# Enclosure_85x58_BHC.net
KiCad netlist of a schematic drawn in EAGLE
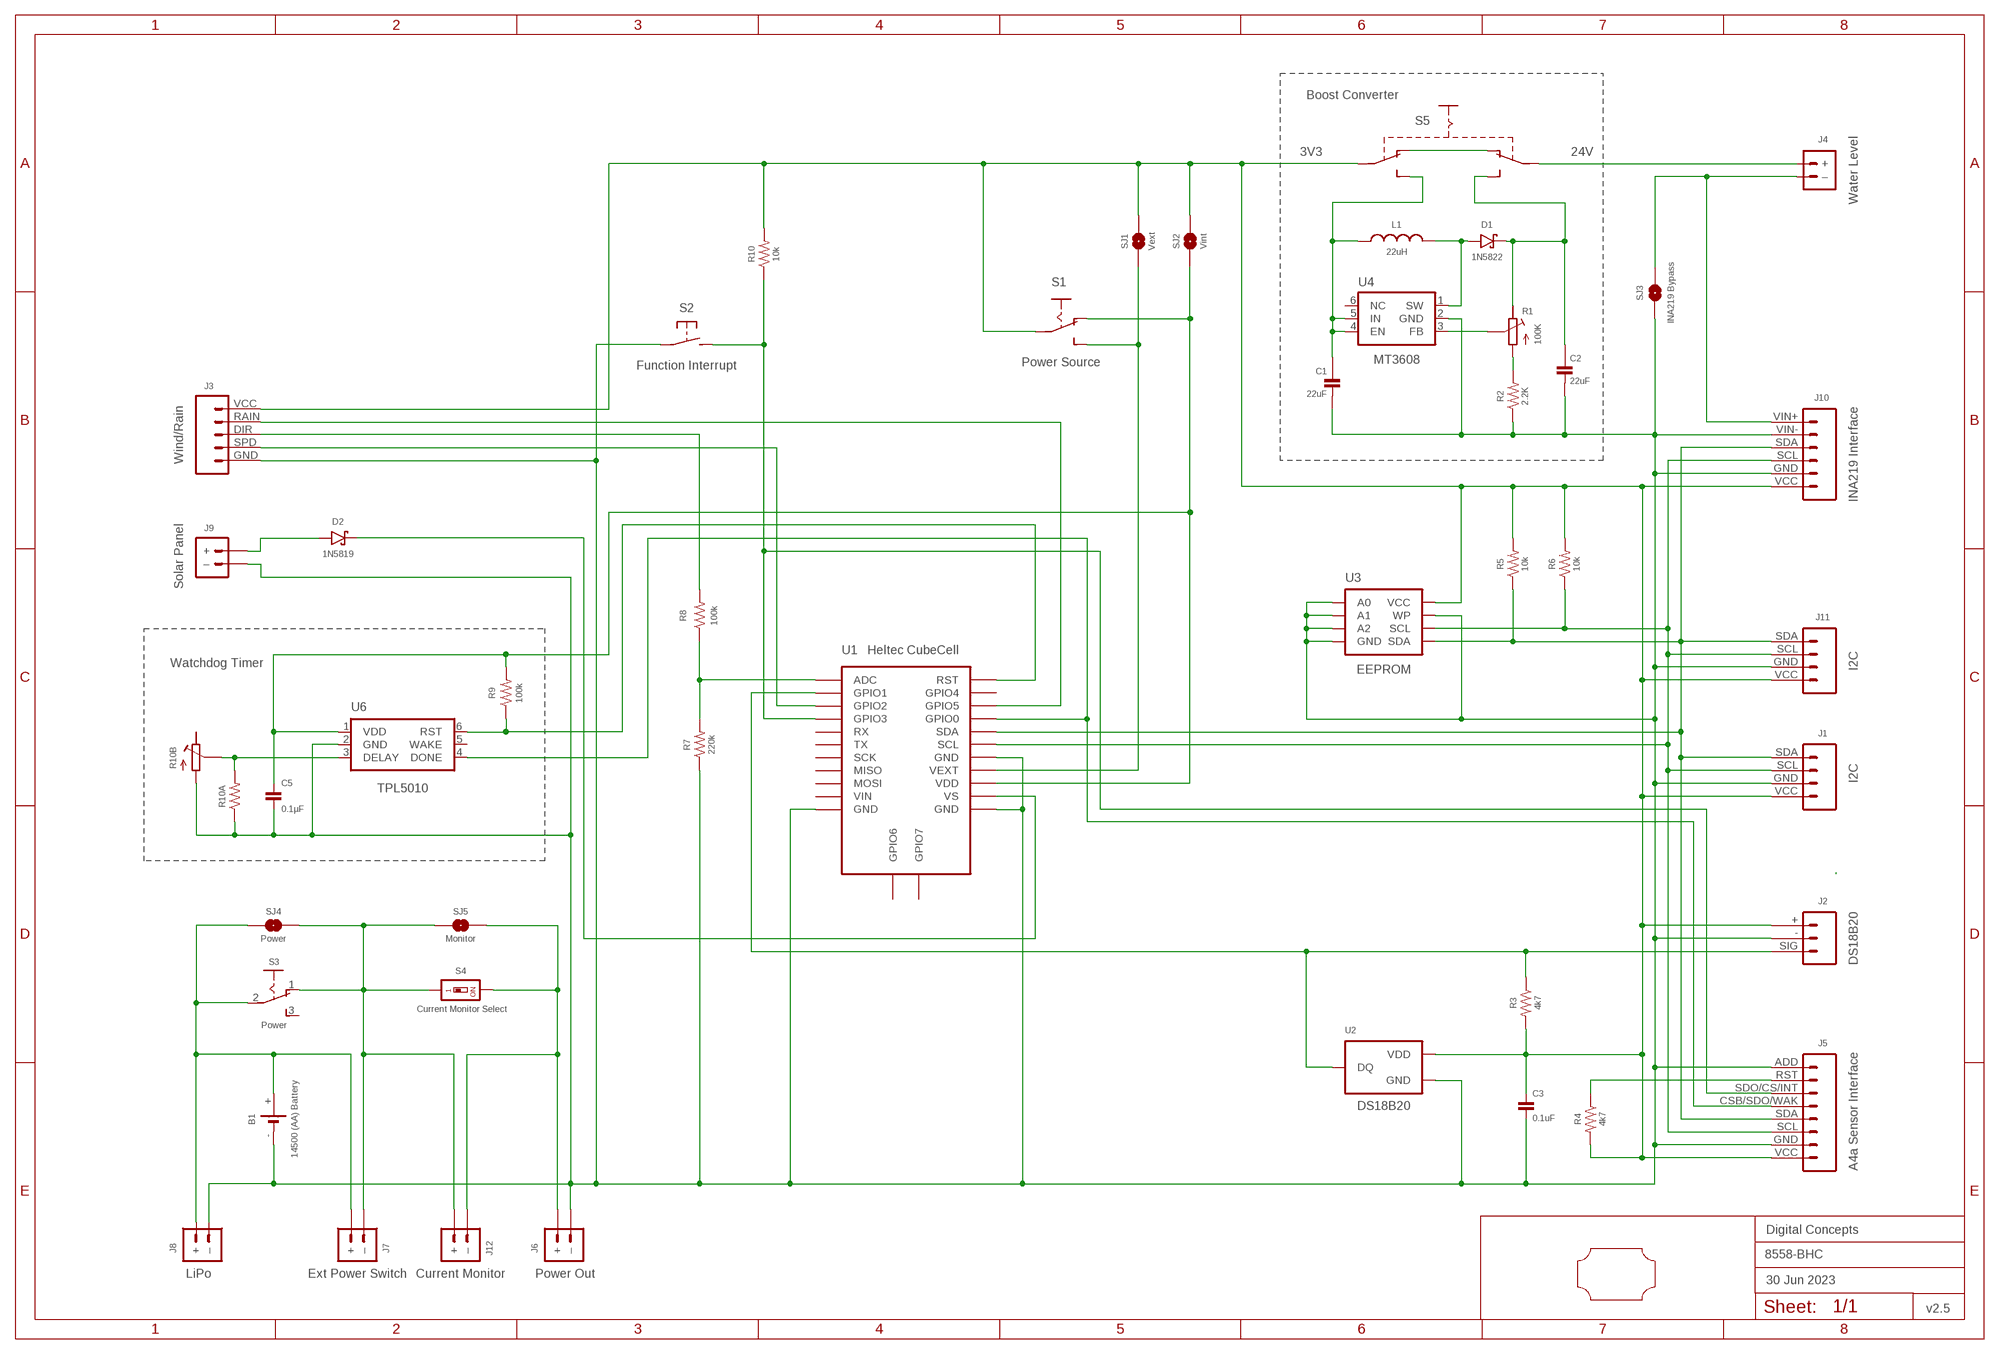
[diagram p0: schematic, sheet 1]

(export (version "E")
  (design (tool "Eeschema 10.0.6"))
  (components
    (comp (ref "B1")
      (value "14500 (AA) Battery")
      (footprint "eagle-import:BATTERY-14500")
      (libsource (lib "eagle-import") (part "BATTERY-HOLDER-14500(AA)"))
    )
    (comp (ref "C1")
      (value "22uF")
      (footprint "eagle-import:C1206")
      (libsource (lib "eagle-import") (part "CAPACITOR-1206"))
    )
    (comp (ref "C2")
      (value "22uF")
      (footprint "eagle-import:C1206")
      (libsource (lib "eagle-import") (part "CAPACITOR-1206"))
    )
    (comp (ref "C3")
      (value "0.1uF")
      (footprint "eagle-import:C0805")
      (libsource (lib "eagle-import") (part "CAPACITOR-0805"))
    )
    (comp (ref "C5")
      (value "0.1µF")
      (footprint "eagle-import:C0805")
      (libsource (lib "eagle-import") (part "CAPACITOR-0805"))
    )
    (comp (ref "D1")
      (value "1N5822")
      (footprint "eagle-import:DIODE_SMB")
      (libsource (lib "eagle-import") (part "DIODE-SCHOTTKY-1N5822"))
    )
    (comp (ref "D2")
      (value "1N5819")
      (footprint "eagle-import:SOD-123")
      (libsource (lib "eagle-import") (part "1N5819-SOD-123"))
    )
    (comp (ref "J1")
      (value "I2C")
      (footprint "eagle-import:JST-PH2.0-4-VERTICAL-I2C")
      (libsource (lib "eagle-import") (part "JST-PH2.0-4-VERTICAL-I2C"))
    )
    (comp (ref "J2")
      (value "DS18B20")
      (footprint "eagle-import:JST-PH2.0-3-VERTICAL")
      (libsource (lib "eagle-import") (part "JST-PH2.0-3-VERTICAL-DS18B20"))
    )
    (comp (ref "J3")
      (value "Wind/Rain")
      (footprint "eagle-import:JST-PH2.0-5-WEATHER")
      (libsource (lib "eagle-import") (part "JST-PH2.0-5-VERTICAL-WEATHER"))
    )
    (comp (ref "J4")
      (value "Water Level")
      (footprint "eagle-import:JST-PH2.0-2-VERTICAL=POWER")
      (libsource (lib "eagle-import") (part "JST-PH2.0-2-VERTICAL"))
    )
    (comp (ref "J5")
      (value "A4a Sensor Interface")
      (footprint "eagle-import:CONN_08-SENSOR")
      (libsource (lib "eagle-import") (part "HEADER-1X8-SENSOR"))
    )
    (comp (ref "J6")
      (value "Power Out")
      (footprint "eagle-import:JST-GH1.25-2-HORIZONTAL")
      (libsource (lib "eagle-import") (part "JST-GH1.25-2-HORIZONTAL-POWER"))
    )
    (comp (ref "J7")
      (value "Ext Power Switch")
      (footprint "eagle-import:JST-PH2.0-2-DUAL-POWER")
      (libsource (lib "eagle-import") (part "JST-PH2.0-2-DUAL-POWERJST-PTH-2"))
    )
    (comp (ref "J8")
      (value "LiPo")
      (footprint "eagle-import:JST-PH2.0-2-HORIZONTAL")
      (libsource (lib "eagle-import") (part "JST-PH2.0-2-MALE-HORIZONTALJST-PTH-2"))
    )
    (comp (ref "J9")
      (value "Solar Panel")
      (footprint "eagle-import:JST-PH2.0-2-DUAL-POWER")
      (libsource (lib "eagle-import") (part "JST-PH2.0-2-DUAL-POWERJST-PTH-2"))
    )
    (comp (ref "J10")
      (value "INA219 Interface")
      (footprint "eagle-import:CONN_06-INA219")
      (libsource (lib "eagle-import") (part "INA219-I2C-MODULE"))
    )
    (comp (ref "J11")
      (value "I2C")
      (footprint "eagle-import:JST-PH2.0-4-HORIZONTAL-I2C")
      (libsource (lib "eagle-import") (part "JST-PH2.0-4-HORIZONTAL-I2C"))
    )
    (comp (ref "J12")
      (value "Current Monitor")
      (footprint "eagle-import:JST-PH2.0-2-HORIZONTAL-POWER")
      (libsource (lib "eagle-import") (part "JST-PH2.0-2-HORIZONTAL-POWERJST-PTH-2"))
    )
    (comp (ref "L1")
      (value "22uH")
      (footprint "eagle-import:CDRH104R+6D28")
      (libsource (lib "eagle-import") (part "INDUCTOR-CDRH104R/6D28L5038P"))
    )
    (comp (ref "R1")
      (value "100K")
      (footprint "eagle-import:RTRIM64P")
      (libsource (lib "eagle-import") (part "RESISTOR-TRIMM-BAOTER-HORIZONTAL"))
    )
    (comp (ref "R2")
      (value "2.2K")
      (footprint "eagle-import:R0805")
      (libsource (lib "eagle-import") (part "RESISTORR0805"))
    )
    (comp (ref "R3")
      (value "4k7")
      (footprint "eagle-import:R0805")
      (libsource (lib "eagle-import") (part "RESISTORR0805"))
    )
    (comp (ref "R4")
      (value "4k7")
      (footprint "eagle-import:R0805")
      (libsource (lib "eagle-import") (part "RESISTORR0805"))
    )
    (comp (ref "R5")
      (value "10k")
      (footprint "eagle-import:R0805")
      (libsource (lib "eagle-import") (part "RESISTORR0805"))
    )
    (comp (ref "R6")
      (value "10k")
      (footprint "eagle-import:R0805")
      (libsource (lib "eagle-import") (part "RESISTORR0805"))
    )
    (comp (ref "R7")
      (value "220k")
      (footprint "eagle-import:R0805")
      (libsource (lib "eagle-import") (part "RESISTORR0805"))
    )
    (comp (ref "R8")
      (value "100k")
      (footprint "eagle-import:R0805")
      (libsource (lib "eagle-import") (part "RESISTORR0805"))
    )
    (comp (ref "R9")
      (value "100k")
      (footprint "eagle-import:R0805")
      (libsource (lib "eagle-import") (part "RESISTORR0805"))
    )
    (comp (ref "R10")
      (value "10k")
      (footprint "eagle-import:R0805")
      (libsource (lib "eagle-import") (part "RESISTORR0805"))
    )
    (comp (ref "R10A")
      (value "RESISTORR0805")
      (footprint "eagle-import:R0805")
      (libsource (lib "eagle-import") (part "RESISTORR0805"))
    )
    (comp (ref "R10B")
      (value "RESISTOR-TRIMM-33")
      (footprint "eagle-import:RTRIM3_3")
      (libsource (lib "eagle-import") (part "RESISTOR-TRIMM-33"))
    )
    (comp (ref "S1")
      (value "Power Source")
      (footprint "eagle-import:SWITCH-SPDT-SMT")
      (libsource (lib "eagle-import") (part "SWITCH-SLIDE-SPDT-SMT"))
    )
    (comp (ref "S2")
      (value "Function Interrupt")
      (footprint "eagle-import:SWITCH-2-PAD")
      (libsource (lib "eagle-import") (part "SWITCH-MOMENTARY-2-PIN"))
    )
    (comp (ref "S3")
      (value "Power")
      (footprint "eagle-import:SWITCH-SLIDE-SPDT")
      (libsource (lib "eagle-import") (part "SWITCH-SLIDE-SPDT"))
    )
    (comp (ref "S4")
      (value "Current Monitor Select")
      (footprint "eagle-import:SMD-001")
      (libsource (lib "eagle-import") (part "SWITCH-DIP-SWS001"))
    )
    (comp (ref "S5")
      (value "SWITCH-SLIDE-DPDT-PTH-S")
      (footprint "eagle-import:SWITCH-DPDT-PTH")
      (libsource (lib "eagle-import") (part "SWITCH-SLIDE-DPDT-PTH-S"))
    )
    (comp (ref "SJ1")
      (value "Vext")
      (footprint "eagle-import:SJ")
      (libsource (lib "eagle-import") (part "SJ"))
    )
    (comp (ref "SJ2")
      (value "Vint")
      (footprint "eagle-import:SJ-VIA-1")
      (libsource (lib "eagle-import") (part "SJ-V-1"))
    )
    (comp (ref "SJ3")
      (value "INA219 Bypass")
      (footprint "eagle-import:SJ")
      (libsource (lib "eagle-import") (part "SJ"))
    )
    (comp (ref "SJ4")
      (value "Power")
      (footprint "eagle-import:SJ")
      (libsource (lib "eagle-import") (part "SJ"))
    )
    (comp (ref "SJ5")
      (value "Monitor")
      (footprint "eagle-import:SJ")
      (libsource (lib "eagle-import") (part "SJ"))
    )
    (comp (ref "U$1")
      (value "PCB-OUTLINE-C-85X58")
      (footprint "eagle-import:PROTO-28X18-OUTLINE-C")
      (libsource (lib "eagle-import") (part "PCB-OUTLINE-C-85X58"))
    )
    (comp (ref "U1")
      (value "Heltec CubeCell")
      (footprint "eagle-import:HELTEC-CUBECELL")
      (libsource (lib "eagle-import") (part "HELTEC-CUBECELL"))
    )
    (comp (ref "U2")
      (value "DS18B20")
      (footprint "eagle-import:TO-92")
      (fields (field (name "MF") "Maxim Integrated"))
      (libsource (lib "eagle-import") (part "THERMOMETER-DS18B20"))
    )
    (comp (ref "U3")
      (value "EEPROM")
      (footprint "eagle-import:SOP-8")
      (libsource (lib "eagle-import") (part "AT24CXX-EEPROM"))
    )
    (comp (ref "U4")
      (value "MT3608")
      (footprint "eagle-import:SOT-23-6@1")
      (libsource (lib "eagle-import") (part "MT3608"))
    )
    (comp (ref "U6")
      (value "TPL5010")
      (footprint "eagle-import:SOT-23-6")
      (libsource (lib "eagle-import") (part "TPL5010DDCR"))
    )
  )
  (nets
    (net (code "1") (name "Net-(D2-PadA)") (class "Default")
      (node (ref "D2") (pin "A") (pinfunction "A_A") (pintype "passive"))
      (node (ref "J9") (pin "+") (pinfunction "+_+") (pintype "power_in"))
    )
    (net (code "2") (name "Net-(D2-PadC)") (class "Default")
      (node (ref "D2") (pin "C") (pinfunction "C_C") (pintype "passive"))
      (node (ref "U1") (pin "VS") (pinfunction "VS_VS") (pintype "bidirectional"))
    )
    (net (code "3") (name "Net-(J1-1)") (class "Default")
      (node (ref "J1") (pin "SDA") (pinfunction "1_SDA") (pintype "passive"))
      (node (ref "J10") (pin "SDA") (pinfunction "4_SDA") (pintype "passive"))
      (node (ref "J11") (pin "SDA") (pinfunction "1_SDA") (pintype "passive"))
      (node (ref "J5") (pin "SDA") (pinfunction "4_SDA") (pintype "passive"))
      (node (ref "R5") (pin "1") (pinfunction "1_1") (pintype "passive"))
      (node (ref "U1") (pin "SDA") (pinfunction "SDA_SDA") (pintype "bidirectional"))
      (node (ref "U3") (pin "P$5") (pinfunction "SDA_P$5") (pintype "bidirectional"))
    )
    (net (code "4") (name "Net-(J1-2)") (class "Default")
      (node (ref "J1") (pin "SCL") (pinfunction "2_SCL") (pintype "passive"))
      (node (ref "J10") (pin "SCL") (pinfunction "3_SCL") (pintype "passive"))
      (node (ref "J11") (pin "SCL") (pinfunction "2_SCL") (pintype "passive"))
      (node (ref "J5") (pin "SCL") (pinfunction "3_SCL") (pintype "passive"))
      (node (ref "R6") (pin "1") (pinfunction "1_1") (pintype "passive"))
      (node (ref "U1") (pin "SCL") (pinfunction "SCL_SCL") (pintype "bidirectional"))
      (node (ref "U3") (pin "P$6") (pinfunction "SCL_P$6") (pintype "bidirectional"))
    )
    (net (code "5") (name "Net-(J1-3)") (class "Default")
      (node (ref "B1") (pin "-") (pinfunction "-_-") (pintype "power_in"))
      (node (ref "C1") (pin "2") (pinfunction "2_2") (pintype "passive"))
      (node (ref "C2") (pin "2") (pinfunction "2_2") (pintype "passive"))
      (node (ref "C3") (pin "2") (pinfunction "2_2") (pintype "passive"))
      (node (ref "C5") (pin "2") (pinfunction "2_2") (pintype "passive"))
      (node (ref "J1") (pin "GND") (pinfunction "3_GND") (pintype "passive"))
      (node (ref "J10") (pin "GND") (pinfunction "2_GND") (pintype "passive"))
      (node (ref "J10") (pin "VIN-") (pinfunction "5_VIN-") (pintype "passive"))
      (node (ref "J11") (pin "GND") (pinfunction "3_GND") (pintype "passive"))
      (node (ref "J2") (pin "-") (pinfunction "2_-") (pintype "passive"))
      (node (ref "J3") (pin "GND") (pinfunction "5_GND") (pintype "passive"))
      (node (ref "J5") (pin "ADD") (pinfunction "8_ADD") (pintype "passive"))
      (node (ref "J5") (pin "GND") (pinfunction "2_GND") (pintype "passive"))
      (node (ref "J6") (pin "-") (pinfunction "–_-") (pintype "power_in"))
      (node (ref "J8") (pin "-") (pinfunction "–_-") (pintype "power_in"))
      (node (ref "J9") (pin "-") (pinfunction "–_-") (pintype "power_in"))
      (node (ref "R10A") (pin "1") (pinfunction "1_1") (pintype "passive"))
      (node (ref "R10B") (pin "1") (pinfunction "A_1") (pintype "passive"))
      (node (ref "R2") (pin "1") (pinfunction "1_1") (pintype "passive"))
      (node (ref "R7") (pin "1") (pinfunction "1_1") (pintype "passive"))
      (node (ref "S2") (pin "P$1") (pinfunction "P_P$1") (pintype "passive"))
      (node (ref "SJ3") (pin "1") (pinfunction "1_1") (pintype "passive"))
      (node (ref "U1") (pin "GND@11") (pinfunction "GND_GND@11") (pintype "bidirectional"))
      (node (ref "U1") (pin "GND@14") (pinfunction "GND_GND@14") (pintype "bidirectional"))
      (node (ref "U1") (pin "GND@18") (pinfunction "GND_GND@18") (pintype "bidirectional"))
      (node (ref "U2") (pin "1") (pinfunction "GND_1") (pintype "power_in"))
      (node (ref "U3") (pin "P$1") (pinfunction "A0_P$1") (pintype "bidirectional"))
      (node (ref "U3") (pin "P$2") (pinfunction "A1_P$2") (pintype "bidirectional"))
      (node (ref "U3") (pin "P$3") (pinfunction "A2_P$3") (pintype "bidirectional"))
      (node (ref "U3") (pin "P$4") (pinfunction "GND_P$4") (pintype "bidirectional"))
      (node (ref "U3") (pin "P$7") (pinfunction "WP_P$7") (pintype "bidirectional"))
      (node (ref "U4") (pin "2") (pinfunction "GND_2") (pintype "power_in"))
      (node (ref "U6") (pin "2") (pinfunction "GND_2") (pintype "power_in"))
    )
    (net (code "6") (name "Net-(J1-4)") (class "Default")
      (node (ref "C3") (pin "1") (pinfunction "1_1") (pintype "passive"))
      (node (ref "J1") (pin "VCC") (pinfunction "4_VCC") (pintype "passive"))
      (node (ref "J10") (pin "VCC") (pinfunction "1_VCC") (pintype "passive"))
      (node (ref "J11") (pin "VCC") (pinfunction "4_VCC") (pintype "passive"))
      (node (ref "J2") (pin "+") (pinfunction "3_+") (pintype "passive"))
      (node (ref "J3") (pin "VCC") (pinfunction "1_VCC") (pintype "passive"))
      (node (ref "J5") (pin "VCC") (pinfunction "1_VCC") (pintype "passive"))
      (node (ref "R10") (pin "2") (pinfunction "2_2") (pintype "passive"))
      (node (ref "R3") (pin "2") (pinfunction "2_2") (pintype "passive"))
      (node (ref "R4") (pin "2") (pinfunction "2_2") (pintype "passive"))
      (node (ref "R5") (pin "2") (pinfunction "2_2") (pintype "passive"))
      (node (ref "R6") (pin "2") (pinfunction "2_2") (pintype "passive"))
      (node (ref "S1") (pin "COMMON") (pinfunction "P_COMMON") (pintype "passive"))
      (node (ref "S5") (pin "P$5") (pinfunction "P2_P$5") (pintype "passive"))
      (node (ref "SJ1") (pin "1") (pinfunction "1_1") (pintype "passive"))
      (node (ref "SJ2") (pin "1") (pinfunction "1_1") (pintype "passive"))
      (node (ref "SJ2") (pin "1@V") (pinfunction "1_1@V") (pintype "passive"))
      (node (ref "U2") (pin "3") (pinfunction "VDD_3") (pintype "power_in"))
      (node (ref "U3") (pin "P$8") (pinfunction "VCC_P$8") (pintype "bidirectional"))
    )
    (net (code "7") (name "Net-(J2-1)") (class "Default")
      (node (ref "J2") (pin "SIG") (pinfunction "1_SIG") (pintype "passive"))
      (node (ref "R3") (pin "1") (pinfunction "1_1") (pintype "passive"))
      (node (ref "U1") (pin "GPIO1") (pinfunction "GPIO1_GPIO1") (pintype "bidirectional"))
      (node (ref "U2") (pin "2") (pinfunction "DQ_2") (pintype "bidirectional"))
    )
    (net (code "8") (name "Net-(J3-2)") (class "Default")
      (node (ref "J3") (pin "RAIN") (pinfunction "2_RAIN") (pintype "passive"))
      (node (ref "U1") (pin "GPIO5") (pinfunction "GPIO5_GPIO5") (pintype "bidirectional"))
    )
    (net (code "9") (name "Net-(J3-3)") (class "Default")
      (node (ref "J3") (pin "DIR") (pinfunction "3_DIR") (pintype "passive"))
      (node (ref "R8") (pin "2") (pinfunction "2_2") (pintype "passive"))
    )
    (net (code "10") (name "Net-(J3-4)") (class "Default")
      (node (ref "J3") (pin "SPD") (pinfunction "4_SPD") (pintype "passive"))
      (node (ref "U1") (pin "GPIO2") (pinfunction "GPIO2_GPIO2") (pintype "bidirectional"))
    )
    (net (code "11") (name "Net-(J5-5)") (class "Default")
      (node (ref "J5") (pin "CSB/SDO/WAK") (pinfunction "5_CSB/SDO/WAK") (pintype "passive"))
      (node (ref "U1") (pin "GPIO0") (pinfunction "GPIO0_GPIO0") (pintype "bidirectional"))
      (node (ref "U6") (pin "4") (pinfunction "DONE_4") (pintype "input"))
    )
    (net (code "12") (name "Net-(J5-6)") (class "Default")
      (node (ref "J5") (pin "SDO/CS/INT") (pinfunction "6_SDO/CS/INT") (pintype "passive"))
      (node (ref "R10") (pin "1") (pinfunction "1_1") (pintype "passive"))
      (node (ref "S2") (pin "P$2") (pinfunction "S_P$2") (pintype "passive"))
      (node (ref "U1") (pin "GPIO3") (pinfunction "GPIO3_GPIO3") (pintype "bidirectional"))
    )
    (net (code "13") (name "Net-(J5-7)") (class "Default")
      (node (ref "J5") (pin "RST") (pinfunction "7_RST") (pintype "passive"))
      (node (ref "R4") (pin "1") (pinfunction "1_1") (pintype "passive"))
    )
    (net (code "14") (name "Net-(J7-–)") (class "Default")
      (node (ref "J12") (pin "+") (pinfunction "+_+") (pintype "power_in"))
      (node (ref "J7") (pin "-") (pinfunction "–_-") (pintype "power_in"))
      (node (ref "S3") (pin "1") (pinfunction "O_1") (pintype "passive"))
      (node (ref "S4") (pin "1") (pinfunction "1_1") (pintype "passive"))
      (node (ref "SJ4") (pin "1") (pinfunction "1_1") (pintype "passive"))
      (node (ref "SJ5") (pin "2") (pinfunction "2_2") (pintype "passive"))
    )
    (net (code "15") (name "Net-(J10-6)") (class "Default")
      (node (ref "J10") (pin "VIN+") (pinfunction "6_VIN+") (pintype "passive"))
      (node (ref "J4") (pin "-") (pinfunction "–_-") (pintype "power_in"))
      (node (ref "SJ3") (pin "2") (pinfunction "2_2") (pintype "passive"))
    )
    (net (code "16") (name "Net-(J12-–)") (class "Default")
      (node (ref "J12") (pin "-") (pinfunction "–_-") (pintype "power_in"))
      (node (ref "J6") (pin "+") (pinfunction "+_+") (pintype "power_in"))
      (node (ref "S4") (pin "2") (pinfunction "2_2") (pintype "passive"))
      (node (ref "SJ5") (pin "1") (pinfunction "1_1") (pintype "passive"))
    )
    (net (code "17") (name "Net-(R1-A)") (class "Default")
      (node (ref "R1") (pin "1") (pinfunction "A_1") (pintype "passive"))
      (node (ref "R2") (pin "2") (pinfunction "2_2") (pintype "passive"))
    )
    (net (code "18") (name "Net-(R1-E)") (class "Default")
      (node (ref "C2") (pin "1") (pinfunction "1_1") (pintype "passive"))
      (node (ref "D1") (pin "C") (pinfunction "C_C") (pintype "passive"))
      (node (ref "R1") (pin "3") (pinfunction "E_3") (pintype "passive"))
      (node (ref "S5") (pin "P$3") (pinfunction "S1_P$3") (pintype "passive"))
    )
    (net (code "19") (name "Net-(R1-S)") (class "Default")
      (node (ref "R1") (pin "2") (pinfunction "S_2") (pintype "passive"))
      (node (ref "U4") (pin "3") (pinfunction "FB_3") (pintype "input"))
    )
    (net (code "20") (name "Net-(R7-Pad2)") (class "Default")
      (node (ref "R7") (pin "2") (pinfunction "2_2") (pintype "passive"))
      (node (ref "R8") (pin "1") (pinfunction "1_1") (pintype "passive"))
      (node (ref "U1") (pin "ADC") (pinfunction "ADC_ADC") (pintype "bidirectional"))
    )
    (net (code "21") (name "Net-(R10B-S)") (class "Default")
      (node (ref "R10A") (pin "2") (pinfunction "2_2") (pintype "passive"))
      (node (ref "R10B") (pin "2") (pinfunction "S_2") (pintype "passive"))
      (node (ref "U6") (pin "3") (pinfunction "DELAY_3") (pintype "input"))
    )
    (net (code "22") (name "Net-(S1-O)") (class "Default")
      (node (ref "C5") (pin "1") (pinfunction "1_1") (pintype "passive"))
      (node (ref "R9") (pin "2") (pinfunction "2_2") (pintype "passive"))
      (node (ref "S1") (pin "P$1") (pinfunction "O_P$1") (pintype "passive"))
      (node (ref "SJ2") (pin "2") (pinfunction "2_2") (pintype "passive"))
      (node (ref "U1") (pin "VDD") (pinfunction "VDD_VDD") (pintype "bidirectional"))
      (node (ref "U6") (pin "1") (pinfunction "VDD_1") (pintype "power_in"))
    )
    (net (code "23") (name "Net-(S1-S)") (class "Default")
      (node (ref "S1") (pin "P$2") (pinfunction "S_P$2") (pintype "passive"))
      (node (ref "SJ1") (pin "2") (pinfunction "2_2") (pintype "passive"))
      (node (ref "U1") (pin "VEXT") (pinfunction "VEXT_VEXT") (pintype "bidirectional"))
    )
    (net (code "24") (name "Net-(S3-P)") (class "Default")
      (node (ref "B1") (pin "+") (pinfunction "+_+") (pintype "power_in"))
      (node (ref "J7") (pin "+") (pinfunction "+_+") (pintype "power_in"))
      (node (ref "J8") (pin "+") (pinfunction "+_+") (pintype "power_in"))
      (node (ref "S3") (pin "2") (pinfunction "P_2") (pintype "passive"))
      (node (ref "SJ4") (pin "2") (pinfunction "2_2") (pintype "passive"))
    )
    (net (code "25") (name "Net-(S5-O1)") (class "Default")
      (node (ref "S5") (pin "P$1") (pinfunction "O1_P$1") (pintype "passive"))
      (node (ref "S5") (pin "P$4") (pinfunction "O2_P$4") (pintype "passive"))
    )
    (net (code "26") (name "Net-(S5-P1)") (class "Default")
      (node (ref "J4") (pin "+") (pinfunction "+_+") (pintype "power_in"))
      (node (ref "S5") (pin "P$2") (pinfunction "P1_P$2") (pintype "passive"))
    )
    (net (code "27") (name "Net-(S5-S2)") (class "Default")
      (node (ref "C1") (pin "1") (pinfunction "1_1") (pintype "passive"))
      (node (ref "L1") (pin "2") (pinfunction "2_2") (pintype "passive"))
      (node (ref "S5") (pin "P$6") (pinfunction "S2_P$6") (pintype "passive"))
      (node (ref "U4") (pin "4") (pinfunction "EN_4") (pintype "input"))
      (node (ref "U4") (pin "5") (pinfunction "IN_5") (pintype "power_in"))
    )
    (net (code "28") (name "Net-(U4-SW)") (class "Default")
      (node (ref "D1") (pin "A") (pinfunction "A_A") (pintype "passive"))
      (node (ref "L1") (pin "1") (pinfunction "1_1") (pintype "passive"))
      (node (ref "U4") (pin "1") (pinfunction "SW_1") (pintype "power_in"))
    )
    (net (code "29") (name "Net-(U6-RST)") (class "Default")
      (node (ref "R9") (pin "1") (pinfunction "1_1") (pintype "passive"))
      (node (ref "U1") (pin "RST") (pinfunction "RST_RST") (pintype "bidirectional"))
      (node (ref "U6") (pin "6") (pinfunction "RST_6") (pintype "output"))
    )
    (net (code "30") (name "unconnected-(R10B-E-Pad3)") (class "Default")
      (node (ref "R10B") (pin "3") (pinfunction "E_3") (pintype "passive"))
    )
    (net (code "31") (name "unconnected-(S3-S-Pad3)") (class "Default")
      (node (ref "S3") (pin "3") (pinfunction "S_3") (pintype "passive"))
    )
    (net (code "32") (name "unconnected-(U1-PadGPIO4)") (class "Default")
      (node (ref "U1") (pin "GPIO4") (pinfunction "GPIO4_GPIO4") (pintype "bidirectional"))
    )
    (net (code "33") (name "unconnected-(U1-PadGPIO6)") (class "Default")
      (node (ref "U1") (pin "GPIO6") (pinfunction "GPIO6_GPIO6") (pintype "bidirectional"))
    )
    (net (code "34") (name "unconnected-(U1-PadGPIO7)") (class "Default")
      (node (ref "U1") (pin "GPIO7") (pinfunction "GPIO7_GPIO7") (pintype "bidirectional"))
    )
    (net (code "35") (name "unconnected-(U1-PadMISO)") (class "Default")
      (node (ref "U1") (pin "MISO") (pinfunction "MISO_MISO") (pintype "bidirectional"))
    )
    (net (code "36") (name "unconnected-(U1-PadMOSI)") (class "Default")
      (node (ref "U1") (pin "MOSI") (pinfunction "MOSI_MOSI") (pintype "bidirectional"))
    )
    (net (code "37") (name "unconnected-(U1-PadRX)") (class "Default")
      (node (ref "U1") (pin "RX") (pinfunction "RX_RX") (pintype "bidirectional"))
    )
    (net (code "38") (name "unconnected-(U1-PadSCK)") (class "Default")
      (node (ref "U1") (pin "SCK") (pinfunction "SCK_SCK") (pintype "bidirectional"))
    )
    (net (code "39") (name "unconnected-(U1-PadTX)") (class "Default")
      (node (ref "U1") (pin "TX") (pinfunction "TX_TX") (pintype "bidirectional"))
    )
    (net (code "40") (name "unconnected-(U1-PadVIN)") (class "Default")
      (node (ref "U1") (pin "VIN") (pinfunction "VIN_VIN") (pintype "bidirectional"))
    )
    (net (code "41") (name "unconnected-(U4-NC-Pad6)") (class "Default")
      (node (ref "U4") (pin "6") (pinfunction "NC_6") (pintype "no_connect"))
    )
    (net (code "42") (name "unconnected-(U6-WAKE-Pad5)") (class "Default")
      (node (ref "U6") (pin "5") (pinfunction "WAKE_5") (pintype "output"))
    )
  )
)
